# ISO-UART_v0_1.net
KiCad netlist of a schematic drawn in EAGLE
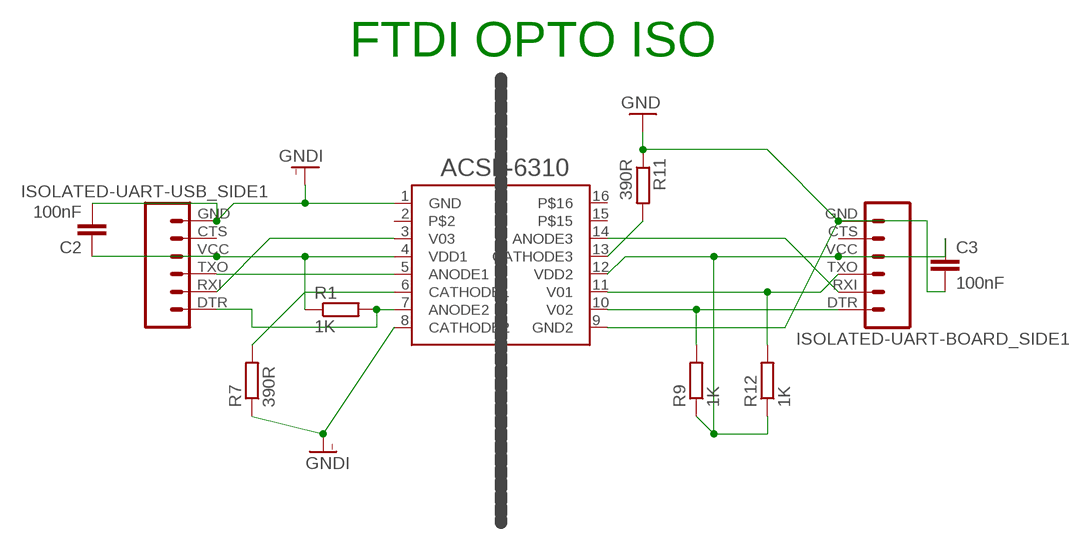
[diagram p0: schematic, sheet 1]

(export (version "E")
  (design (tool "Eeschema 10.0.6"))
  (components
    (comp (ref "ACSL-6310")
      (value "ACSL-6310")
      (footprint "eagle-import:SO16")
      (libsource (lib "eagle-import") (part "ACSL-6310"))
    )
    (comp (ref "C2")
      (value "100nF")
      (footprint "eagle-import:C0603")
      (libsource (lib "eagle-import") (part "C-EUC0603"))
    )
    (comp (ref "C3")
      (value "100nF")
      (footprint "eagle-import:C0603")
      (libsource (lib "eagle-import") (part "C-EUC0603"))
    )
    (comp (ref "ISOLATED-UART-BOARD_SIDE1")
      (value "2211S-06G")
      (footprint "eagle-import:FTDI_BASIC")
      (fields (field (name "MF") "MULTICOMP"))
      (libsource (lib "eagle-import") (part "FTDI_BASICPTH"))
    )
    (comp (ref "ISOLATED-UART-USB_SIDE1")
      (value "2211S-06G")
      (footprint "eagle-import:FTDI_BASIC")
      (fields (field (name "MF") "MULTICOMP"))
      (libsource (lib "eagle-import") (part "FTDI_BASICPTH"))
    )
    (comp (ref "R1")
      (value "1K")
      (footprint "eagle-import:R0603")
      (libsource (lib "eagle-import") (part "R-EU_R0603"))
    )
    (comp (ref "R7")
      (value "390R")
      (footprint "eagle-import:R0603")
      (libsource (lib "eagle-import") (part "R-EU_R0603"))
    )
    (comp (ref "R9")
      (value "1K")
      (footprint "eagle-import:R0603")
      (libsource (lib "eagle-import") (part "R-EU_R0603"))
    )
    (comp (ref "R11")
      (value "390R")
      (footprint "eagle-import:R0603")
      (libsource (lib "eagle-import") (part "R-EU_R0603"))
    )
    (comp (ref "R12")
      (value "1K")
      (footprint "eagle-import:R0603")
      (libsource (lib "eagle-import") (part "R-EU_R0603"))
    )
  )
  (nets
    (net (code "1") (name "GND") (class "Default")
      (node (ref "ACSL-6310") (pin "9") (pinfunction "GND2_9") (pintype "output"))
      (node (ref "C3") (pin "2") (pinfunction "2_2") (pintype "passive"))
      (node (ref "ISOLATED-UART-BOARD_SIDE1") (pin "GND") (pinfunction "6_GND") (pintype "passive"))
      (node (ref "R11") (pin "1") (pinfunction "1_1") (pintype "passive"))
    )
    (net (code "2") (name "GNDI") (class "Default")
      (node (ref "ACSL-6310") (pin "1") (pinfunction "GND_1") (pintype "output"))
      (node (ref "ACSL-6310") (pin "8") (pinfunction "CATHODE2_8") (pintype "output"))
      (node (ref "C2") (pin "2") (pinfunction "2_2") (pintype "passive"))
      (node (ref "ISOLATED-UART-USB_SIDE1") (pin "GND") (pinfunction "6_GND") (pintype "passive"))
      (node (ref "R7") (pin "1") (pinfunction "1_1") (pintype "passive"))
    )
    (net (code "3") (name "Net-(ACSL-6310-ANODE1)") (class "Default")
      (node (ref "ACSL-6310") (pin "5") (pinfunction "ANODE1_5") (pintype "output"))
      (node (ref "ISOLATED-UART-USB_SIDE1") (pin "TXO") (pinfunction "3_TXO") (pintype "passive"))
    )
    (net (code "4") (name "Net-(ACSL-6310-ANODE2)") (class "Default")
      (node (ref "ACSL-6310") (pin "7") (pinfunction "ANODE2_7") (pintype "output"))
      (node (ref "ISOLATED-UART-USB_SIDE1") (pin "DTR") (pinfunction "1_DTR") (pintype "passive"))
      (node (ref "R1") (pin "2") (pinfunction "2_2") (pintype "passive"))
    )
    (net (code "5") (name "Net-(ACSL-6310-ANODE3)") (class "Default")
      (node (ref "ACSL-6310") (pin "14") (pinfunction "ANODE3_14") (pintype "output"))
      (node (ref "ISOLATED-UART-BOARD_SIDE1") (pin "RXI") (pinfunction "2_RXI") (pintype "passive"))
    )
    (net (code "6") (name "Net-(ACSL-6310-CATHODE1)") (class "Default")
      (node (ref "ACSL-6310") (pin "6") (pinfunction "CATHODE1_6") (pintype "output"))
      (node (ref "R7") (pin "2") (pinfunction "2_2") (pintype "passive"))
    )
    (net (code "7") (name "Net-(ACSL-6310-CATHODE3)") (class "Default")
      (node (ref "ACSL-6310") (pin "13") (pinfunction "CATHODE3_13") (pintype "output"))
      (node (ref "R11") (pin "2") (pinfunction "2_2") (pintype "passive"))
    )
    (net (code "8") (name "Net-(ACSL-6310-V01)") (class "Default")
      (node (ref "ACSL-6310") (pin "11") (pinfunction "V01_11") (pintype "output"))
      (node (ref "ISOLATED-UART-BOARD_SIDE1") (pin "TXO") (pinfunction "3_TXO") (pintype "passive"))
      (node (ref "R12") (pin "2") (pinfunction "2_2") (pintype "passive"))
    )
    (net (code "9") (name "Net-(ACSL-6310-V02)") (class "Default")
      (node (ref "ACSL-6310") (pin "10") (pinfunction "V02_10") (pintype "output"))
      (node (ref "ISOLATED-UART-BOARD_SIDE1") (pin "DTR") (pinfunction "1_DTR") (pintype "passive"))
      (node (ref "R9") (pin "2") (pinfunction "2_2") (pintype "passive"))
    )
    (net (code "10") (name "Net-(ACSL-6310-V03)") (class "Default")
      (node (ref "ACSL-6310") (pin "3") (pinfunction "V03_3") (pintype "output"))
      (node (ref "ISOLATED-UART-USB_SIDE1") (pin "RXI") (pinfunction "2_RXI") (pintype "passive"))
    )
    (net (code "11") (name "Net-(ACSL-6310-VDD1)") (class "Default")
      (node (ref "ACSL-6310") (pin "4") (pinfunction "VDD1_4") (pintype "output"))
      (node (ref "C2") (pin "1") (pinfunction "1_1") (pintype "passive"))
      (node (ref "ISOLATED-UART-USB_SIDE1") (pin "VCC") (pinfunction "4_VCC") (pintype "passive"))
      (node (ref "R1") (pin "1") (pinfunction "1_1") (pintype "passive"))
    )
    (net (code "12") (name "Net-(ACSL-6310-VDD2)") (class "Default")
      (node (ref "ACSL-6310") (pin "12") (pinfunction "VDD2_12") (pintype "output"))
      (node (ref "C3") (pin "1") (pinfunction "1_1") (pintype "passive"))
      (node (ref "ISOLATED-UART-BOARD_SIDE1") (pin "VCC") (pinfunction "4_VCC") (pintype "passive"))
      (node (ref "R12") (pin "1") (pinfunction "1_1") (pintype "passive"))
      (node (ref "R9") (pin "1") (pinfunction "1_1") (pintype "passive"))
    )
    (net (code "13") (name "unconnected-(ACSL-6310-P$2-Pad2)") (class "Default")
      (node (ref "ACSL-6310") (pin "2") (pinfunction "P$2_2") (pintype "output"))
    )
    (net (code "14") (name "unconnected-(ACSL-6310-P$15-Pad15)") (class "Default")
      (node (ref "ACSL-6310") (pin "15") (pinfunction "P$15_15") (pintype "output"))
    )
    (net (code "15") (name "unconnected-(ACSL-6310-P$16-Pad16)") (class "Default")
      (node (ref "ACSL-6310") (pin "16") (pinfunction "P$16_16") (pintype "output"))
    )
    (net (code "16") (name "unconnected-(ISOLATED-UART-BOARD_SIDE1-5-PadCTS)") (class "Default")
      (node (ref "ISOLATED-UART-BOARD_SIDE1") (pin "CTS") (pinfunction "5_CTS") (pintype "passive"))
    )
    (net (code "17") (name "unconnected-(ISOLATED-UART-USB_SIDE1-5-PadCTS)") (class "Default")
      (node (ref "ISOLATED-UART-USB_SIDE1") (pin "CTS") (pinfunction "5_CTS") (pintype "passive"))
    )
  )
)
